# analog_mcu.net
KiCad netlist of a schematic drawn in Altium Designer
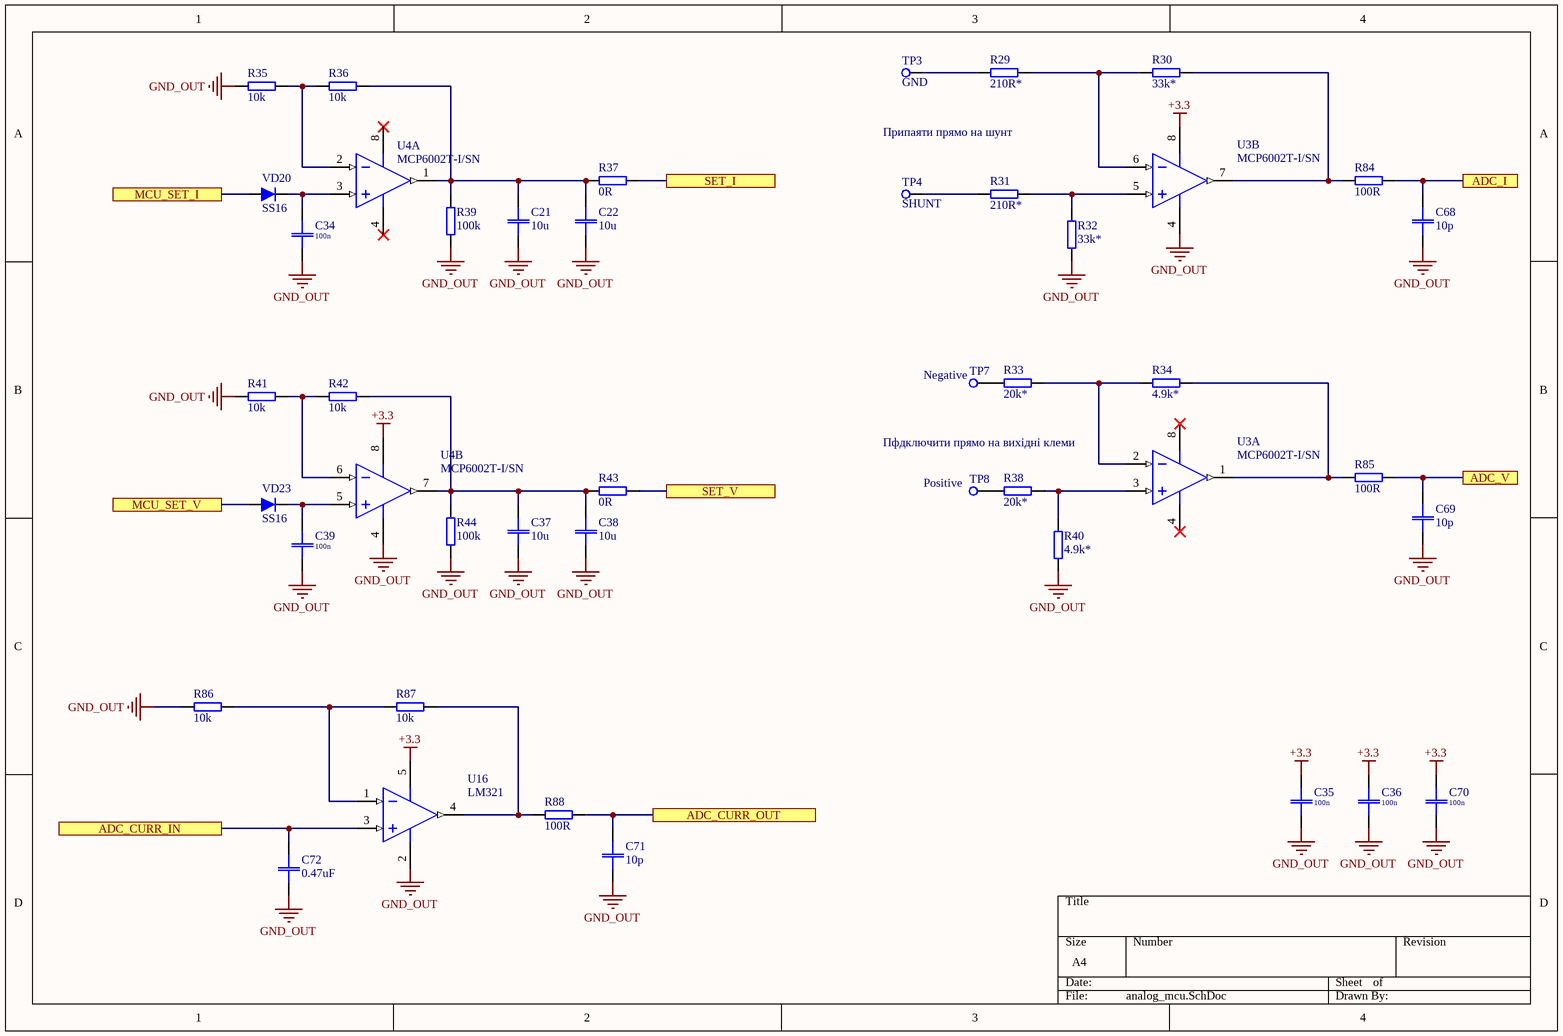
[diagram p0: analog_mcu.SchDoc]

(export (version "E")
  (design (tool "Eeschema 10.0.6"))
  (components
    (comp (ref "C21") (value "10u") (footprint "CAP: 0805") (libsource (lib "PASSIVE") (part "C_SMD")))
    (comp (ref "C22") (value "10u") (footprint "CAP: 0805") (libsource (lib "PASSIVE") (part "C_SMD")))
    (comp (ref "C34")
      (value "100n")
      (footprint "C0603")
      (description "SMD-0603")
      (libsource (lib "SMD-RCL") (part "C-0603"))
    )
    (comp (ref "C35")
      (value "100n")
      (footprint "C0603")
      (description "SMD-0603")
      (libsource (lib "SMD-RCL") (part "C-0603"))
    )
    (comp (ref "C36")
      (value "100n")
      (footprint "C0603")
      (description "SMD-0603")
      (libsource (lib "SMD-RCL") (part "C-0603"))
    )
    (comp (ref "C37") (value "10u") (footprint "CAP: 0805") (libsource (lib "PASSIVE") (part "C_SMD")))
    (comp (ref "C38") (value "10u") (footprint "CAP: 0805") (libsource (lib "PASSIVE") (part "C_SMD")))
    (comp (ref "C39")
      (value "100n")
      (footprint "C0603")
      (description "SMD-0603")
      (libsource (lib "SMD-RCL") (part "C-0603"))
    )
    (comp (ref "C68") (value "10p") (footprint "CAP: 0603") (libsource (lib "PASSIVE") (part "C_SMD")))
    (comp (ref "C69") (value "10p") (footprint "CAP: 0603") (libsource (lib "PASSIVE") (part "C_SMD")))
    (comp (ref "C70")
      (value "100n")
      (footprint "C0603")
      (description "SMD-0603")
      (libsource (lib "SMD-RCL") (part "C-0603"))
    )
    (comp (ref "C71") (value "10p") (footprint "CAP: 0603") (libsource (lib "PASSIVE") (part "C_SMD")))
    (comp (ref "C72") (value "0.47uF") (footprint "CAP: 0603") (libsource (lib "PASSIVE") (part "C_SMD")))
    (comp (ref "R29") (value "210R*") (footprint "RES: 0603") (libsource (lib "PASSIVE") (part "R_SMD")))
    (comp (ref "R30") (value "33k*") (footprint "RES: 0603") (libsource (lib "PASSIVE") (part "R_SMD")))
    (comp (ref "R31") (value "210R*") (footprint "RES: 0603") (libsource (lib "PASSIVE") (part "R_SMD")))
    (comp (ref "R32") (value "33k*") (footprint "RES: 0603") (libsource (lib "PASSIVE") (part "R_SMD")))
    (comp (ref "R33") (value "20k*") (footprint "RES: 0603") (libsource (lib "PASSIVE") (part "R_SMD")))
    (comp (ref "R34") (value "4.9k*") (footprint "RES: 0603") (libsource (lib "PASSIVE") (part "R_SMD")))
    (comp (ref "R35") (value "10k") (footprint "RES: 0603") (libsource (lib "PASSIVE") (part "R_SMD")))
    (comp (ref "R36") (value "10k") (footprint "RES: 0603") (libsource (lib "PASSIVE") (part "R_SMD")))
    (comp (ref "R37") (value "0R") (footprint "RES: 0603") (libsource (lib "PASSIVE") (part "R_SMD")))
    (comp (ref "R38") (value "20k*") (footprint "RES: 0603") (libsource (lib "PASSIVE") (part "R_SMD")))
    (comp (ref "R39") (value "100k") (footprint "RES: 0603") (libsource (lib "PASSIVE") (part "R_SMD")))
    (comp (ref "R40") (value "4.9k*") (footprint "RES: 0603") (libsource (lib "PASSIVE") (part "R_SMD")))
    (comp (ref "R41") (value "10k") (footprint "RES: 0603") (libsource (lib "PASSIVE") (part "R_SMD")))
    (comp (ref "R42") (value "10k") (footprint "RES: 0603") (libsource (lib "PASSIVE") (part "R_SMD")))
    (comp (ref "R43") (value "0R") (footprint "RES: 0603") (libsource (lib "PASSIVE") (part "R_SMD")))
    (comp (ref "R44") (value "100k") (footprint "RES: 0603") (libsource (lib "PASSIVE") (part "R_SMD")))
    (comp (ref "R84") (value "100R") (footprint "RES: 0603") (libsource (lib "PASSIVE") (part "R_SMD")))
    (comp (ref "R85") (value "100R") (footprint "RES: 0603") (libsource (lib "PASSIVE") (part "R_SMD")))
    (comp (ref "R86") (value "10k") (footprint "RES: 0603") (libsource (lib "PASSIVE") (part "R_SMD")))
    (comp (ref "R87") (value "10k") (footprint "RES: 0603") (libsource (lib "PASSIVE") (part "R_SMD")))
    (comp (ref "R88") (value "100R") (footprint "RES: 0603") (libsource (lib "PASSIVE") (part "R_SMD")))
    (comp (ref "TP3")
      (value "GND")
      (footprint "TP: TEST POINT DIP")
      (libsource (lib "OTHER") (part "TEST POINT"))
    )
    (comp (ref "TP4")
      (value "SHUNT")
      (footprint "TP: TEST POINT DIP")
      (libsource (lib "OTHER") (part "TEST POINT"))
    )
    (comp (ref "TP7")
      (value "Negative")
      (footprint "TP: TEST POINT DIP")
      (libsource (lib "OTHER") (part "TEST POINT"))
    )
    (comp (ref "TP8")
      (value "Positive")
      (footprint "TP: TEST POINT DIP")
      (libsource (lib "OTHER") (part "TEST POINT"))
    )
    (comp (ref "U3")
      (value "MCP6002T-I/SN")
      (footprint "SOIC-SN8_N")
      (description "1 MHz, Low-Power Operational Amplifier, 8-Pin SOIC, Industrial Temperature, Tape and Reel")
      (fields (field (name "PUBLISHER") "Altium Limited"))
      (libsource (lib "Microchip Linear Devices") (part "MCP6002T-I/SN"))
    )
    (comp (ref "U4")
      (value "MCP6002T-I/SN")
      (footprint "SOIC-SN8_N")
      (description "1 MHz, Low-Power Operational Amplifier, 8-Pin SOIC, Industrial Temperature, Tape and Reel")
      (fields (field (name "PUBLISHER") "Altium Limited"))
      (libsource (lib "Microchip Linear Devices") (part "MCP6002T-I/SN"))
    )
    (comp (ref "U16") (value "LM321") (footprint "SOT23-5") (libsource (lib "ANALOG") (part "LMV611")))
    (comp (ref "VD20")
      (value "SS16")
      (footprint "DIODE: SOD123")
      (libsource (lib "DIODES") (part "DIODE_SMD"))
    )
    (comp (ref "VD23")
      (value "SS16")
      (footprint "DIODE: SOD123")
      (libsource (lib "DIODES") (part "DIODE_SMD"))
    )
  )
  (nets
    (net (code "1") (name "+3.3") (class "Default")
      (node (ref "C35") (pin "1") (pinfunction "1_1") (pintype "passive"))
      (node (ref "C36") (pin "1") (pinfunction "1_1") (pintype "passive"))
      (node (ref "C70") (pin "1") (pinfunction "1_1") (pintype "passive"))
      (node (ref "U16") (pin "5") (pinfunction "V+_5") (pintype "power_in"))
      (node (ref "U3") (pin "8") (pinfunction "VDD_8") (pintype "power_in"))
      (node (ref "U4") (pin "8") (pinfunction "VDD_8") (pintype "power_in"))
    )
    (net (code "2") (name "/ADC_CURR_IN") (class "Default")
      (node (ref "C72") (pin "2") (pinfunction "2_2") (pintype "passive"))
      (node (ref "U16") (pin "3") (pinfunction "IN+_3") (pintype "input"))
    )
    (net (code "3") (name "/ADC_CURR_OUT") (class "Default")
      (node (ref "C71") (pin "2") (pinfunction "2_2") (pintype "passive"))
      (node (ref "R88") (pin "2") (pinfunction "2_2") (pintype "passive"))
    )
    (net (code "4") (name "/ADC_I") (class "Default")
      (node (ref "C68") (pin "2") (pinfunction "2_2") (pintype "passive"))
      (node (ref "R84") (pin "2") (pinfunction "2_2") (pintype "passive"))
    )
    (net (code "5") (name "/ADC_V") (class "Default")
      (node (ref "C69") (pin "2") (pinfunction "2_2") (pintype "passive"))
      (node (ref "R85") (pin "2") (pinfunction "2_2") (pintype "passive"))
    )
    (net (code "6") (name "/MCU_SET_I") (class "Default")
      (node (ref "VD20") (pin "1") (pinfunction "A_1") (pintype "passive"))
    )
    (net (code "7") (name "/MCU_SET_V") (class "Default")
      (node (ref "VD23") (pin "1") (pinfunction "A_1") (pintype "passive"))
    )
    (net (code "8") (name "/SET_I") (class "Default")
      (node (ref "R37") (pin "1") (pinfunction "1_1") (pintype "passive"))
    )
    (net (code "9") (name "/SET_V") (class "Default")
      (node (ref "R43") (pin "1") (pinfunction "1_1") (pintype "passive"))
    )
    (net (code "10") (name "GND_OUT") (class "Default")
      (node (ref "C21") (pin "1") (pinfunction "1_1") (pintype "passive"))
      (node (ref "C22") (pin "1") (pinfunction "1_1") (pintype "passive"))
      (node (ref "C34") (pin "1") (pinfunction "1_1") (pintype "passive"))
      (node (ref "C35") (pin "2") (pinfunction "2_2") (pintype "passive"))
      (node (ref "C36") (pin "2") (pinfunction "2_2") (pintype "passive"))
      (node (ref "C37") (pin "1") (pinfunction "1_1") (pintype "passive"))
      (node (ref "C38") (pin "1") (pinfunction "1_1") (pintype "passive"))
      (node (ref "C39") (pin "1") (pinfunction "1_1") (pintype "passive"))
      (node (ref "C68") (pin "1") (pinfunction "1_1") (pintype "passive"))
      (node (ref "C69") (pin "1") (pinfunction "1_1") (pintype "passive"))
      (node (ref "C70") (pin "2") (pinfunction "2_2") (pintype "passive"))
      (node (ref "C71") (pin "1") (pinfunction "1_1") (pintype "passive"))
      (node (ref "C72") (pin "1") (pinfunction "1_1") (pintype "passive"))
      (node (ref "R32") (pin "1") (pinfunction "1_1") (pintype "passive"))
      (node (ref "R35") (pin "1") (pinfunction "1_1") (pintype "passive"))
      (node (ref "R39") (pin "1") (pinfunction "1_1") (pintype "passive"))
      (node (ref "R40") (pin "2") (pinfunction "2_2") (pintype "passive"))
      (node (ref "R41") (pin "1") (pinfunction "1_1") (pintype "passive"))
      (node (ref "R44") (pin "1") (pinfunction "1_1") (pintype "passive"))
      (node (ref "R86") (pin "1") (pinfunction "1_1") (pintype "passive"))
      (node (ref "U16") (pin "2") (pinfunction "V-_2") (pintype "power_in"))
      (node (ref "U3") (pin "4") (pinfunction "VSS_4") (pintype "power_in"))
      (node (ref "U4") (pin "4") (pinfunction "VSS_4") (pintype "power_in"))
    )
    (net (code "11") (name "Net-(R29-Pad1)") (class "Default")
      (node (ref "R29") (pin "1") (pinfunction "1_1") (pintype "passive"))
      (node (ref "TP3") (pin "1") (pintype "passive"))
    )
    (net (code "12") (name "Net-(R31-Pad1)") (class "Default")
      (node (ref "R31") (pin "1") (pinfunction "1_1") (pintype "passive"))
      (node (ref "TP4") (pin "1") (pintype "passive"))
    )
    (net (code "13") (name "Net-(R33-Pad1)") (class "Default")
      (node (ref "R33") (pin "1") (pinfunction "1_1") (pintype "passive"))
      (node (ref "TP7") (pin "1") (pintype "passive"))
    )
    (net (code "14") (name "Net-(R38-Pad1)") (class "Default")
      (node (ref "R38") (pin "1") (pinfunction "1_1") (pintype "passive"))
      (node (ref "TP8") (pin "1") (pintype "passive"))
    )
    (net (code "15") (name "Net-(U3A-VINA+)") (class "Default")
      (node (ref "R38") (pin "2") (pinfunction "2_2") (pintype "passive"))
      (node (ref "R40") (pin "1") (pinfunction "1_1") (pintype "passive"))
      (node (ref "U3") (pin "3") (pinfunction "VINA+_3") (pintype "input"))
    )
    (net (code "16") (name "Net-(U3A-VINA-)") (class "Default")
      (node (ref "R33") (pin "2") (pinfunction "2_2") (pintype "passive"))
      (node (ref "R34") (pin "1") (pinfunction "1_1") (pintype "passive"))
      (node (ref "U3") (pin "2") (pinfunction "VINA-_2") (pintype "input"))
    )
    (net (code "17") (name "Net-(U3A-VOUTA)") (class "Default")
      (node (ref "R34") (pin "2") (pinfunction "2_2") (pintype "passive"))
      (node (ref "R85") (pin "1") (pinfunction "1_1") (pintype "passive"))
      (node (ref "U3") (pin "1") (pinfunction "VOUTA_1") (pintype "output"))
    )
    (net (code "18") (name "Net-(U3B-VINB+)") (class "Default")
      (node (ref "R31") (pin "2") (pinfunction "2_2") (pintype "passive"))
      (node (ref "R32") (pin "2") (pinfunction "2_2") (pintype "passive"))
      (node (ref "U3") (pin "5") (pinfunction "VINB+_5") (pintype "input"))
    )
    (net (code "19") (name "Net-(U3B-VINB-)") (class "Default")
      (node (ref "R29") (pin "2") (pinfunction "2_2") (pintype "passive"))
      (node (ref "R30") (pin "1") (pinfunction "1_1") (pintype "passive"))
      (node (ref "U3") (pin "6") (pinfunction "VINB-_6") (pintype "input"))
    )
    (net (code "20") (name "Net-(U3B-VOUTB)") (class "Default")
      (node (ref "R30") (pin "2") (pinfunction "2_2") (pintype "passive"))
      (node (ref "R84") (pin "1") (pinfunction "1_1") (pintype "passive"))
      (node (ref "U3") (pin "7") (pinfunction "VOUTB_7") (pintype "output"))
    )
    (net (code "21") (name "Net-(U4A-VINA+)") (class "Default")
      (node (ref "C34") (pin "2") (pinfunction "2_2") (pintype "passive"))
      (node (ref "U4") (pin "3") (pinfunction "VINA+_3") (pintype "input"))
      (node (ref "VD20") (pin "2") (pinfunction "C_2") (pintype "passive"))
    )
    (net (code "22") (name "Net-(U4A-VINA-)") (class "Default")
      (node (ref "R35") (pin "2") (pinfunction "2_2") (pintype "passive"))
      (node (ref "R36") (pin "1") (pinfunction "1_1") (pintype "passive"))
      (node (ref "U4") (pin "2") (pinfunction "VINA-_2") (pintype "input"))
    )
    (net (code "23") (name "Net-(U4A-VOUTA)") (class "Default")
      (node (ref "C21") (pin "2") (pinfunction "2_2") (pintype "passive"))
      (node (ref "C22") (pin "2") (pinfunction "2_2") (pintype "passive"))
      (node (ref "R36") (pin "2") (pinfunction "2_2") (pintype "passive"))
      (node (ref "R37") (pin "2") (pinfunction "2_2") (pintype "passive"))
      (node (ref "R39") (pin "2") (pinfunction "2_2") (pintype "passive"))
      (node (ref "U4") (pin "1") (pinfunction "VOUTA_1") (pintype "output"))
    )
    (net (code "24") (name "Net-(U4B-VINB+)") (class "Default")
      (node (ref "C39") (pin "2") (pinfunction "2_2") (pintype "passive"))
      (node (ref "U4") (pin "5") (pinfunction "VINB+_5") (pintype "input"))
      (node (ref "VD23") (pin "2") (pinfunction "C_2") (pintype "passive"))
    )
    (net (code "25") (name "Net-(U4B-VINB-)") (class "Default")
      (node (ref "R41") (pin "2") (pinfunction "2_2") (pintype "passive"))
      (node (ref "R42") (pin "1") (pinfunction "1_1") (pintype "passive"))
      (node (ref "U4") (pin "6") (pinfunction "VINB-_6") (pintype "input"))
    )
    (net (code "26") (name "Net-(U4B-VOUTB)") (class "Default")
      (node (ref "C37") (pin "2") (pinfunction "2_2") (pintype "passive"))
      (node (ref "C38") (pin "2") (pinfunction "2_2") (pintype "passive"))
      (node (ref "R42") (pin "2") (pinfunction "2_2") (pintype "passive"))
      (node (ref "R43") (pin "2") (pinfunction "2_2") (pintype "passive"))
      (node (ref "R44") (pin "2") (pinfunction "2_2") (pintype "passive"))
      (node (ref "U4") (pin "7") (pinfunction "VOUTB_7") (pintype "output"))
    )
    (net (code "27") (name "Net-(U16-IN-)") (class "Default")
      (node (ref "R86") (pin "2") (pinfunction "2_2") (pintype "passive"))
      (node (ref "R87") (pin "1") (pinfunction "1_1") (pintype "passive"))
      (node (ref "U16") (pin "1") (pinfunction "IN-_1") (pintype "input"))
    )
    (net (code "28") (name "Net-(U16-OUT)") (class "Default")
      (node (ref "R87") (pin "2") (pinfunction "2_2") (pintype "passive"))
      (node (ref "R88") (pin "1") (pinfunction "1_1") (pintype "passive"))
      (node (ref "U16") (pin "4") (pinfunction "OUT_4") (pintype "output"))
    )
    (net (code "29") (name "unconnected-(U3A-VDD-Pad8)") (class "Default")
      (node (ref "U3") (pin "8") (pinfunction "VDD_8") (pintype "power_in+no_connect"))
    )
    (net (code "30") (name "unconnected-(U3A-VSS-Pad4)") (class "Default")
      (node (ref "U3") (pin "4") (pinfunction "VSS_4") (pintype "power_in+no_connect"))
    )
    (net (code "31") (name "unconnected-(U4A-VDD-Pad8)") (class "Default")
      (node (ref "U4") (pin "8") (pinfunction "VDD_8") (pintype "power_in+no_connect"))
    )
    (net (code "32") (name "unconnected-(U4A-VSS-Pad4)") (class "Default")
      (node (ref "U4") (pin "4") (pinfunction "VSS_4") (pintype "power_in+no_connect"))
    )
  )
)
